# CTD_sch.net
KiCad netlist of a schematic drawn in EAGLE
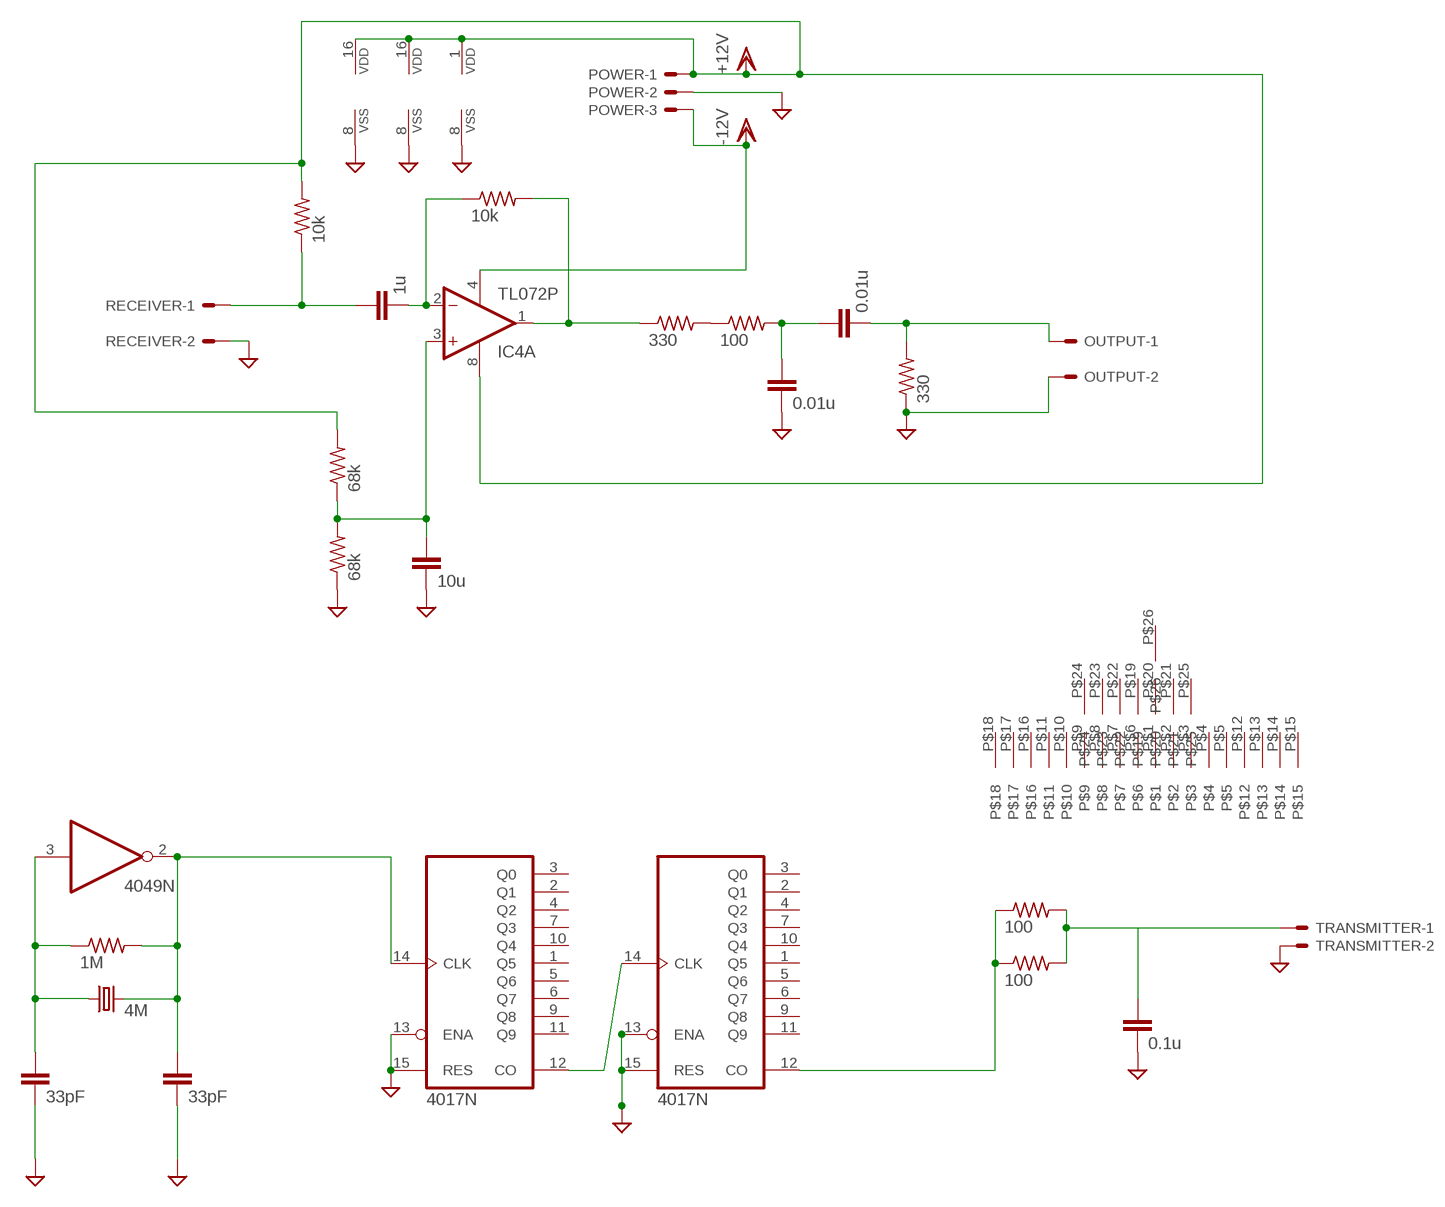
[diagram p0: schematic, sheet 1]

(export (version "E")
  (design (tool "Eeschema 10.0.6"))
  (components
    (comp (ref "C1")
      (value "33pF")
      (footprint "eagle-import:C5B3.5")
      (libsource (lib "eagle-import") (part "C5/3.5"))
    )
    (comp (ref "C2")
      (value "33pF")
      (footprint "eagle-import:C5B3.5")
      (libsource (lib "eagle-import") (part "C5/3.5"))
    )
    (comp (ref "C3")
      (value "0.1u")
      (footprint "eagle-import:C5B3.5")
      (libsource (lib "eagle-import") (part "C5/3.5"))
    )
    (comp (ref "C4")
      (value "10u")
      (footprint "eagle-import:C5B3.5")
      (libsource (lib "eagle-import") (part "C5/3.5"))
    )
    (comp (ref "C5")
      (value "1u")
      (footprint "eagle-import:C5B3.5")
      (libsource (lib "eagle-import") (part "C5/3.5"))
    )
    (comp (ref "C6")
      (value "0.01u")
      (footprint "eagle-import:C5B3.5")
      (libsource (lib "eagle-import") (part "C5/3.5"))
    )
    (comp (ref "C7")
      (value "0.01u")
      (footprint "eagle-import:C5B3.5")
      (libsource (lib "eagle-import") (part "C5/3.5"))
    )
    (comp (ref "IC1")
      (value "4017N")
      (footprint "eagle-import:DIL16")
      (libsource (lib "eagle-import") (part "4017N"))
    )
    (comp (ref "IC2")
      (value "4017N")
      (footprint "eagle-import:DIL16")
      (libsource (lib "eagle-import") (part "4017N"))
    )
    (comp (ref "IC3")
      (value "4049N")
      (footprint "eagle-import:DIL16")
      (libsource (lib "eagle-import") (part "4049N"))
    )
    (comp (ref "IC4")
      (value "TL072P")
      (footprint "eagle-import:DIL08")
      (libsource (lib "eagle-import") (part "TL072P"))
    )
    (comp (ref "OUTPUT")
      (value "C-GRID-02-70543")
      (footprint "eagle-import:70543-02")
      (fields (field (name "MF") "MOLEX"))
      (libsource (lib "eagle-import") (part "C-GRID-02-70543"))
    )
    (comp (ref "POWER")
      (value "C-GRID-03-70543")
      (footprint "eagle-import:70543-03")
      (fields (field (name "MF") "MOLEX"))
      (libsource (lib "eagle-import") (part "C-GRID-03-70543"))
    )
    (comp (ref "Q1")
      (value "4M")
      (footprint "eagle-import:HC49U-V")
      (libsource (lib "eagle-import") (part "CRYSTALHC49U-V"))
    )
    (comp (ref "R1")
      (value "1M")
      (footprint "eagle-import:0207_12")
      (libsource (lib "eagle-import") (part "R-US_0207/12"))
    )
    (comp (ref "R2")
      (value "100")
      (footprint "eagle-import:0207_12")
      (libsource (lib "eagle-import") (part "R-US_0207/12"))
    )
    (comp (ref "R3")
      (value "100")
      (footprint "eagle-import:0207_12")
      (libsource (lib "eagle-import") (part "R-US_0207/12"))
    )
    (comp (ref "R4")
      (value "68k")
      (footprint "eagle-import:0207_12")
      (libsource (lib "eagle-import") (part "R-US_0207/12"))
    )
    (comp (ref "R5")
      (value "10k")
      (footprint "eagle-import:0207_12")
      (libsource (lib "eagle-import") (part "R-US_0207/12"))
    )
    (comp (ref "R6")
      (value "10k")
      (footprint "eagle-import:0207_12")
      (libsource (lib "eagle-import") (part "R-US_0207/12"))
    )
    (comp (ref "R7")
      (value "68k")
      (footprint "eagle-import:0207_12")
      (libsource (lib "eagle-import") (part "R-US_0207/12"))
    )
    (comp (ref "R8")
      (value "330")
      (footprint "eagle-import:0207_12")
      (libsource (lib "eagle-import") (part "R-US_0207/12"))
    )
    (comp (ref "R9")
      (value "100")
      (footprint "eagle-import:0207_12")
      (libsource (lib "eagle-import") (part "R-US_0207/12"))
    )
    (comp (ref "R10")
      (value "330")
      (footprint "eagle-import:0207_12")
      (libsource (lib "eagle-import") (part "R-US_0207/12"))
    )
    (comp (ref "RECEIVER")
      (value "C-GRID-02-70543")
      (footprint "eagle-import:70543-02")
      (fields (field (name "MF") "MOLEX"))
      (libsource (lib "eagle-import") (part "C-GRID-02-70543"))
    )
    (comp (ref "TRANSMITTER")
      (value "C-GRID-02-70543")
      (footprint "eagle-import:70543-02")
      (fields (field (name "MF") "MOLEX"))
      (libsource (lib "eagle-import") (part "C-GRID-02-70543"))
    )
    (comp (ref "U$1")
      (value "G-11G-11")
      (footprint "eagle-import:G-11")
      (libsource (lib "eagle-import") (part "G-11G-11"))
    )
  )
  (nets
    (net (code "1") (name "+12V") (class "Default")
      (node (ref "IC1") (pin "16") (pinfunction "VDD_16") (pintype "power_in"))
      (node (ref "IC2") (pin "16") (pinfunction "VDD_16") (pintype "power_in"))
      (node (ref "IC3") (pin "1") (pinfunction "VDD_1") (pintype "power_in"))
      (node (ref "IC4") (pin "8") (pinfunction "V+_8") (pintype "power_in"))
      (node (ref "POWER") (pin "1") (pinfunction "S_1") (pintype "passive"))
      (node (ref "R5") (pin "2") (pinfunction "2_2") (pintype "passive"))
      (node (ref "R7") (pin "2") (pinfunction "2_2") (pintype "passive"))
    )
    (net (code "2") (name "-12V") (class "Default")
      (node (ref "IC4") (pin "4") (pinfunction "V-_4") (pintype "power_in"))
      (node (ref "POWER") (pin "3") (pinfunction "S_3") (pintype "passive"))
    )
    (net (code "3") (name "GND") (class "Default")
      (node (ref "C1") (pin "2") (pinfunction "2_2") (pintype "passive"))
      (node (ref "C2") (pin "2") (pinfunction "2_2") (pintype "passive"))
      (node (ref "C3") (pin "2") (pinfunction "2_2") (pintype "passive"))
      (node (ref "C4") (pin "2") (pinfunction "2_2") (pintype "passive"))
      (node (ref "C6") (pin "2") (pinfunction "2_2") (pintype "passive"))
      (node (ref "IC1") (pin "13") (pinfunction "ENA_13") (pintype "input"))
      (node (ref "IC1") (pin "15") (pinfunction "RES_15") (pintype "input"))
      (node (ref "IC1") (pin "8") (pinfunction "VSS_8") (pintype "power_in"))
      (node (ref "IC2") (pin "13") (pinfunction "ENA_13") (pintype "input"))
      (node (ref "IC2") (pin "15") (pinfunction "RES_15") (pintype "input"))
      (node (ref "IC2") (pin "8") (pinfunction "VSS_8") (pintype "power_in"))
      (node (ref "IC3") (pin "8") (pinfunction "VSS_8") (pintype "power_in"))
      (node (ref "OUTPUT") (pin "2") (pinfunction "S_2") (pintype "passive"))
      (node (ref "POWER") (pin "2") (pinfunction "S_2") (pintype "passive"))
      (node (ref "R10") (pin "1") (pinfunction "1_1") (pintype "passive"))
      (node (ref "R4") (pin "1") (pinfunction "1_1") (pintype "passive"))
      (node (ref "RECEIVER") (pin "2") (pinfunction "S_2") (pintype "passive"))
      (node (ref "TRANSMITTER") (pin "2") (pinfunction "S_2") (pintype "passive"))
    )
    (net (code "4") (name "Net-(C6-Pad1)") (class "Default")
      (node (ref "C6") (pin "1") (pinfunction "1_1") (pintype "passive"))
      (node (ref "C7") (pin "1") (pinfunction "1_1") (pintype "passive"))
      (node (ref "R9") (pin "2") (pinfunction "2_2") (pintype "passive"))
    )
    (net (code "5") (name "Net-(IC1A-CLK)") (class "Default")
      (node (ref "C1") (pin "1") (pinfunction "1_1") (pintype "passive"))
      (node (ref "IC1") (pin "14") (pinfunction "CLK_14") (pintype "input"))
      (node (ref "IC3") (pin "2") (pinfunction "O_2") (pintype "output"))
      (node (ref "Q1") (pin "2") (pinfunction "2_2") (pintype "passive"))
      (node (ref "R1") (pin "2") (pinfunction "2_2") (pintype "passive"))
    )
    (net (code "6") (name "Net-(IC1A-CO)") (class "Default")
      (node (ref "IC1") (pin "12") (pinfunction "CO_12") (pintype "output"))
      (node (ref "IC2") (pin "14") (pinfunction "CLK_14") (pintype "input"))
    )
    (net (code "7") (name "Net-(IC2A-CO)") (class "Default")
      (node (ref "IC2") (pin "12") (pinfunction "CO_12") (pintype "output"))
      (node (ref "R2") (pin "1") (pinfunction "1_1") (pintype "passive"))
      (node (ref "R3") (pin "1") (pinfunction "1_1") (pintype "passive"))
    )
    (net (code "8") (name "Net-(IC3A-I)") (class "Default")
      (node (ref "C2") (pin "1") (pinfunction "1_1") (pintype "passive"))
      (node (ref "IC3") (pin "3") (pinfunction "I_3") (pintype "input"))
      (node (ref "Q1") (pin "1") (pinfunction "1_1") (pintype "passive"))
      (node (ref "R1") (pin "1") (pinfunction "1_1") (pintype "passive"))
    )
    (net (code "9") (name "Net-(IC4A-+IN)") (class "Default")
      (node (ref "C4") (pin "1") (pinfunction "1_1") (pintype "passive"))
      (node (ref "IC4") (pin "3") (pinfunction "+IN_3") (pintype "input"))
      (node (ref "R4") (pin "2") (pinfunction "2_2") (pintype "passive"))
      (node (ref "R7") (pin "1") (pinfunction "1_1") (pintype "passive"))
    )
    (net (code "10") (name "Net-(IC4A--IN)") (class "Default")
      (node (ref "C5") (pin "2") (pinfunction "2_2") (pintype "passive"))
      (node (ref "IC4") (pin "2") (pinfunction "-IN_2") (pintype "input"))
      (node (ref "R6") (pin "1") (pinfunction "1_1") (pintype "passive"))
    )
    (net (code "11") (name "Net-(IC4A-OUT)") (class "Default")
      (node (ref "IC4") (pin "1") (pinfunction "OUT_1") (pintype "output"))
      (node (ref "R6") (pin "2") (pinfunction "2_2") (pintype "passive"))
      (node (ref "R8") (pin "1") (pinfunction "1_1") (pintype "passive"))
    )
    (net (code "12") (name "Net-(OUTPUTA-S)") (class "Default")
      (node (ref "C7") (pin "2") (pinfunction "2_2") (pintype "passive"))
      (node (ref "OUTPUT") (pin "1") (pinfunction "S_1") (pintype "passive"))
      (node (ref "R10") (pin "2") (pinfunction "2_2") (pintype "passive"))
    )
    (net (code "13") (name "Net-(R8-Pad2)") (class "Default")
      (node (ref "R8") (pin "2") (pinfunction "2_2") (pintype "passive"))
      (node (ref "R9") (pin "1") (pinfunction "1_1") (pintype "passive"))
    )
    (net (code "14") (name "Net-(RECEIVERA-S)") (class "Default")
      (node (ref "C5") (pin "1") (pinfunction "1_1") (pintype "passive"))
      (node (ref "R5") (pin "1") (pinfunction "1_1") (pintype "passive"))
      (node (ref "RECEIVER") (pin "1") (pinfunction "S_1") (pintype "passive"))
    )
    (net (code "15") (name "Net-(TRANSMITTERA-S)") (class "Default")
      (node (ref "C3") (pin "1") (pinfunction "1_1") (pintype "passive"))
      (node (ref "R2") (pin "2") (pinfunction "2_2") (pintype "passive"))
      (node (ref "R3") (pin "2") (pinfunction "2_2") (pintype "passive"))
      (node (ref "TRANSMITTER") (pin "1") (pinfunction "S_1") (pintype "passive"))
    )
    (net (code "16") (name "unconnected-(IC1A-Q0-Pad3)") (class "Default")
      (node (ref "IC1") (pin "3") (pinfunction "Q0_3") (pintype "output"))
    )
    (net (code "17") (name "unconnected-(IC1A-Q1-Pad2)") (class "Default")
      (node (ref "IC1") (pin "2") (pinfunction "Q1_2") (pintype "output"))
    )
    (net (code "18") (name "unconnected-(IC1A-Q2-Pad4)") (class "Default")
      (node (ref "IC1") (pin "4") (pinfunction "Q2_4") (pintype "output"))
    )
    (net (code "19") (name "unconnected-(IC1A-Q3-Pad7)") (class "Default")
      (node (ref "IC1") (pin "7") (pinfunction "Q3_7") (pintype "output"))
    )
    (net (code "20") (name "unconnected-(IC1A-Q4-Pad10)") (class "Default")
      (node (ref "IC1") (pin "10") (pinfunction "Q4_10") (pintype "output"))
    )
    (net (code "21") (name "unconnected-(IC1A-Q5-Pad1)") (class "Default")
      (node (ref "IC1") (pin "1") (pinfunction "Q5_1") (pintype "output"))
    )
    (net (code "22") (name "unconnected-(IC1A-Q6-Pad5)") (class "Default")
      (node (ref "IC1") (pin "5") (pinfunction "Q6_5") (pintype "output"))
    )
    (net (code "23") (name "unconnected-(IC1A-Q7-Pad6)") (class "Default")
      (node (ref "IC1") (pin "6") (pinfunction "Q7_6") (pintype "output"))
    )
    (net (code "24") (name "unconnected-(IC1A-Q8-Pad9)") (class "Default")
      (node (ref "IC1") (pin "9") (pinfunction "Q8_9") (pintype "output"))
    )
    (net (code "25") (name "unconnected-(IC1A-Q9-Pad11)") (class "Default")
      (node (ref "IC1") (pin "11") (pinfunction "Q9_11") (pintype "output"))
    )
    (net (code "26") (name "unconnected-(IC2A-Q0-Pad3)") (class "Default")
      (node (ref "IC2") (pin "3") (pinfunction "Q0_3") (pintype "output"))
    )
    (net (code "27") (name "unconnected-(IC2A-Q1-Pad2)") (class "Default")
      (node (ref "IC2") (pin "2") (pinfunction "Q1_2") (pintype "output"))
    )
    (net (code "28") (name "unconnected-(IC2A-Q2-Pad4)") (class "Default")
      (node (ref "IC2") (pin "4") (pinfunction "Q2_4") (pintype "output"))
    )
    (net (code "29") (name "unconnected-(IC2A-Q3-Pad7)") (class "Default")
      (node (ref "IC2") (pin "7") (pinfunction "Q3_7") (pintype "output"))
    )
    (net (code "30") (name "unconnected-(IC2A-Q4-Pad10)") (class "Default")
      (node (ref "IC2") (pin "10") (pinfunction "Q4_10") (pintype "output"))
    )
    (net (code "31") (name "unconnected-(IC2A-Q5-Pad1)") (class "Default")
      (node (ref "IC2") (pin "1") (pinfunction "Q5_1") (pintype "output"))
    )
    (net (code "32") (name "unconnected-(IC2A-Q6-Pad5)") (class "Default")
      (node (ref "IC2") (pin "5") (pinfunction "Q6_5") (pintype "output"))
    )
    (net (code "33") (name "unconnected-(IC2A-Q7-Pad6)") (class "Default")
      (node (ref "IC2") (pin "6") (pinfunction "Q7_6") (pintype "output"))
    )
    (net (code "34") (name "unconnected-(IC2A-Q8-Pad9)") (class "Default")
      (node (ref "IC2") (pin "9") (pinfunction "Q8_9") (pintype "output"))
    )
    (net (code "35") (name "unconnected-(IC2A-Q9-Pad11)") (class "Default")
      (node (ref "IC2") (pin "11") (pinfunction "Q9_11") (pintype "output"))
    )
    (net (code "36") (name "unconnected-(U$1-PadP$1)") (class "Default")
      (node (ref "U$1") (pin "P$1") (pinfunction "P$1_P$1") (pintype "bidirectional"))
    )
    (net (code "37") (name "unconnected-(U$1-PadP$2)") (class "Default")
      (node (ref "U$1") (pin "P$2") (pinfunction "P$2_P$2") (pintype "bidirectional"))
    )
    (net (code "38") (name "unconnected-(U$1-PadP$3)") (class "Default")
      (node (ref "U$1") (pin "P$3") (pinfunction "P$3_P$3") (pintype "bidirectional"))
    )
    (net (code "39") (name "unconnected-(U$1-PadP$4)") (class "Default")
      (node (ref "U$1") (pin "P$4") (pinfunction "P$4_P$4") (pintype "bidirectional"))
    )
    (net (code "40") (name "unconnected-(U$1-PadP$5)") (class "Default")
      (node (ref "U$1") (pin "P$5") (pinfunction "P$5_P$5") (pintype "bidirectional"))
    )
    (net (code "41") (name "unconnected-(U$1-PadP$6)") (class "Default")
      (node (ref "U$1") (pin "P$6") (pinfunction "P$6_P$6") (pintype "bidirectional"))
    )
    (net (code "42") (name "unconnected-(U$1-PadP$7)") (class "Default")
      (node (ref "U$1") (pin "P$7") (pinfunction "P$7_P$7") (pintype "bidirectional"))
    )
    (net (code "43") (name "unconnected-(U$1-PadP$8)") (class "Default")
      (node (ref "U$1") (pin "P$8") (pinfunction "P$8_P$8") (pintype "bidirectional"))
    )
    (net (code "44") (name "unconnected-(U$1-PadP$9)") (class "Default")
      (node (ref "U$1") (pin "P$9") (pinfunction "P$9_P$9") (pintype "bidirectional"))
    )
    (net (code "45") (name "unconnected-(U$1-PadP$10)") (class "Default")
      (node (ref "U$1") (pin "P$10") (pinfunction "P$10_P$10") (pintype "bidirectional"))
    )
    (net (code "46") (name "unconnected-(U$1-PadP$11)") (class "Default")
      (node (ref "U$1") (pin "P$11") (pinfunction "P$11_P$11") (pintype "bidirectional"))
    )
    (net (code "47") (name "unconnected-(U$1-PadP$12)") (class "Default")
      (node (ref "U$1") (pin "P$12") (pinfunction "P$12_P$12") (pintype "bidirectional"))
    )
    (net (code "48") (name "unconnected-(U$1-PadP$13)") (class "Default")
      (node (ref "U$1") (pin "P$13") (pinfunction "P$13_P$13") (pintype "bidirectional"))
    )
    (net (code "49") (name "unconnected-(U$1-PadP$14)") (class "Default")
      (node (ref "U$1") (pin "P$14") (pinfunction "P$14_P$14") (pintype "bidirectional"))
    )
    (net (code "50") (name "unconnected-(U$1-PadP$15)") (class "Default")
      (node (ref "U$1") (pin "P$15") (pinfunction "P$15_P$15") (pintype "bidirectional"))
    )
    (net (code "51") (name "unconnected-(U$1-PadP$16)") (class "Default")
      (node (ref "U$1") (pin "P$16") (pinfunction "P$16_P$16") (pintype "bidirectional"))
    )
    (net (code "52") (name "unconnected-(U$1-PadP$17)") (class "Default")
      (node (ref "U$1") (pin "P$17") (pinfunction "P$17_P$17") (pintype "bidirectional"))
    )
    (net (code "53") (name "unconnected-(U$1-PadP$18)") (class "Default")
      (node (ref "U$1") (pin "P$18") (pinfunction "P$18_P$18") (pintype "bidirectional"))
    )
    (net (code "54") (name "unconnected-(U$1-PadP$19)") (class "Default")
      (node (ref "U$1") (pin "P$19") (pinfunction "P$19_P$19") (pintype "bidirectional"))
    )
    (net (code "55") (name "unconnected-(U$1-PadP$20)") (class "Default")
      (node (ref "U$1") (pin "P$20") (pinfunction "P$20_P$20") (pintype "bidirectional"))
    )
    (net (code "56") (name "unconnected-(U$1-PadP$21)") (class "Default")
      (node (ref "U$1") (pin "P$21") (pinfunction "P$21_P$21") (pintype "bidirectional"))
    )
    (net (code "57") (name "unconnected-(U$1-PadP$22)") (class "Default")
      (node (ref "U$1") (pin "P$22") (pinfunction "P$22_P$22") (pintype "bidirectional"))
    )
    (net (code "58") (name "unconnected-(U$1-PadP$23)") (class "Default")
      (node (ref "U$1") (pin "P$23") (pinfunction "P$23_P$23") (pintype "bidirectional"))
    )
    (net (code "59") (name "unconnected-(U$1-PadP$24)") (class "Default")
      (node (ref "U$1") (pin "P$24") (pinfunction "P$24_P$24") (pintype "bidirectional"))
    )
    (net (code "60") (name "unconnected-(U$1-PadP$25)") (class "Default")
      (node (ref "U$1") (pin "P$25") (pinfunction "P$25_P$25") (pintype "bidirectional"))
    )
    (net (code "61") (name "unconnected-(U$1-PadP$26)") (class "Default")
      (node (ref "U$1") (pin "P$26") (pinfunction "P$26_P$26") (pintype "bidirectional"))
    )
  )
)
